# fpga-bank7.net
KiCad netlist of a schematic drawn in Altium Designer
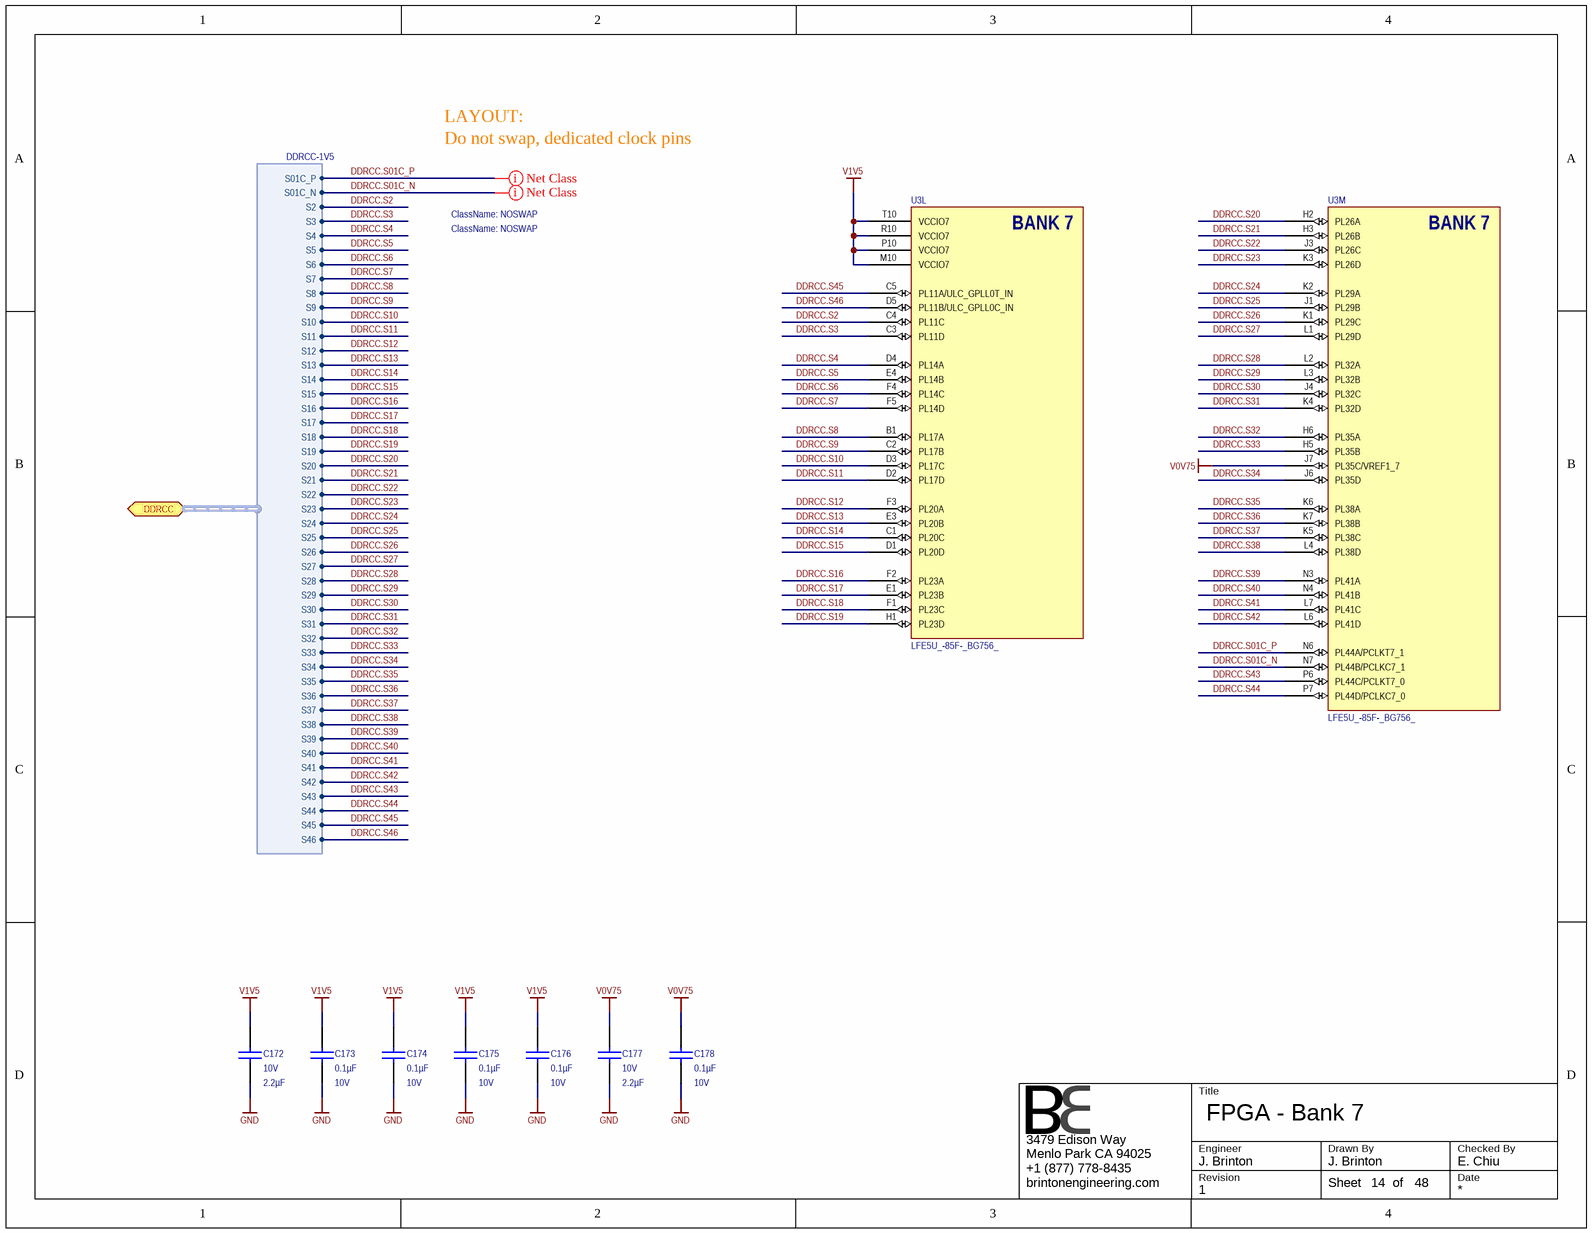
[diagram p0: fpga-bank7.SchDoc]

(export (version "E")
  (design (tool "Eeschema 10.0.6"))
  (components
    (comp (ref "C172")
      (value "GRM188R71A225KE15D")
      (footprint "CAPC1608X90N")
      (description "CAP CER 2.2UF 10V 10% X7R 0603")
      (fields
        (field (name "MANUFACTURER") "Murata Electronics North America")
        (field (name "TOLERANCE") "±10%")
        (field (name "VOLTAGE - RATED") "10V")
        (field (name "CAPACITANCE") "2.2µF")
      )
      (libsource (lib "murata") (part "GRM188R71A225KE15D"))
    )
    (comp (ref "C173")
      (value "GRM155R71A104KA01J")
      (footprint "CAPC1005X56N")
      (description "CAP CER 0.1UF 10V 10% X7R 0402")
      (fields
        (field (name "MANUFACTURER") "Murata Electronics North America")
        (field (name "TOLERANCE") "±10%")
        (field (name "CAPACITANCE") "0.1µF")
        (field (name "VOLTAGE - RATED") "10V")
      )
      (libsource (lib "murata") (part "GRM155R71A104KA01J"))
    )
    (comp (ref "C174")
      (value "GRM155R71A104KA01J")
      (footprint "CAPC1005X56N")
      (description "CAP CER 0.1UF 10V 10% X7R 0402")
      (fields
        (field (name "MANUFACTURER") "Murata Electronics North America")
        (field (name "TOLERANCE") "±10%")
        (field (name "CAPACITANCE") "0.1µF")
        (field (name "VOLTAGE - RATED") "10V")
      )
      (libsource (lib "murata") (part "GRM155R71A104KA01J"))
    )
    (comp (ref "C175")
      (value "GRM155R71A104KA01J")
      (footprint "CAPC1005X56N")
      (description "CAP CER 0.1UF 10V 10% X7R 0402")
      (fields
        (field (name "MANUFACTURER") "Murata Electronics North America")
        (field (name "TOLERANCE") "±10%")
        (field (name "CAPACITANCE") "0.1µF")
        (field (name "VOLTAGE - RATED") "10V")
      )
      (libsource (lib "murata") (part "GRM155R71A104KA01J"))
    )
    (comp (ref "C176")
      (value "GRM155R71A104KA01J")
      (footprint "CAPC1005X56N")
      (description "CAP CER 0.1UF 10V 10% X7R 0402")
      (fields
        (field (name "MANUFACTURER") "Murata Electronics North America")
        (field (name "TOLERANCE") "±10%")
        (field (name "CAPACITANCE") "0.1µF")
        (field (name "VOLTAGE - RATED") "10V")
      )
      (libsource (lib "murata") (part "GRM155R71A104KA01J"))
    )
    (comp (ref "C177")
      (value "GRM188R71A225KE15D")
      (footprint "CAPC1608X90N")
      (description "CAP CER 2.2UF 10V 10% X7R 0603")
      (fields
        (field (name "MANUFACTURER") "Murata Electronics North America")
        (field (name "TOLERANCE") "±10%")
        (field (name "VOLTAGE - RATED") "10V")
        (field (name "CAPACITANCE") "2.2µF")
      )
      (libsource (lib "murata") (part "GRM188R71A225KE15D"))
    )
    (comp (ref "C178")
      (value "GRM155R71A104KA01J")
      (footprint "CAPC1005X56N")
      (description "CAP CER 0.1UF 10V 10% X7R 0402")
      (fields
        (field (name "MANUFACTURER") "Murata Electronics North America")
        (field (name "TOLERANCE") "±10%")
        (field (name "CAPACITANCE") "0.1µF")
        (field (name "VOLTAGE - RATED") "10V")
      )
      (libsource (lib "murata") (part "GRM155R71A104KA01J"))
    )
    (comp (ref "U3")
      (value "LFE5U_-85F-_BG756_")
      (footprint "lattice:caBGA756")
      (description "ECP5 FPGA, 85k LUT, 756-caBGA")
      (fields (field (name "MANUFACTURER") "Lattice Semiconductor"))
      (libsource (lib "lattice") (part "LFE5U_-85F-_BG756_"))
    )
  )
  (nets
    (net (code "2") (name "/DDRCC.S01C_N") (class "Default")
      (node (ref "U3") (pin "N7") (pinfunction "PL44B/PCLKC7_1_N7") (pintype "bidirectional"))
    )
    (net (code "3") (name "/DDRCC.S01C_P") (class "Default")
      (node (ref "U3") (pin "N6") (pinfunction "PL44A/PCLKT7_1_N6") (pintype "bidirectional"))
    )
    (net (code "4") (name "/DDRCC.S2") (class "Default")
      (node (ref "U3") (pin "C4") (pinfunction "PL11C_C4") (pintype "bidirectional"))
    )
    (net (code "5") (name "/DDRCC.S3") (class "Default")
      (node (ref "U3") (pin "C3") (pinfunction "PL11D_C3") (pintype "bidirectional"))
    )
    (net (code "6") (name "/DDRCC.S4") (class "Default")
      (node (ref "U3") (pin "D4") (pinfunction "PL14A_D4") (pintype "bidirectional"))
    )
    (net (code "7") (name "/DDRCC.S5") (class "Default")
      (node (ref "U3") (pin "E4") (pinfunction "PL14B_E4") (pintype "bidirectional"))
    )
    (net (code "8") (name "/DDRCC.S6") (class "Default")
      (node (ref "U3") (pin "F4") (pinfunction "PL14C_F4") (pintype "bidirectional"))
    )
    (net (code "9") (name "/DDRCC.S7") (class "Default")
      (node (ref "U3") (pin "F5") (pinfunction "PL14D_F5") (pintype "bidirectional"))
    )
    (net (code "10") (name "/DDRCC.S8") (class "Default")
      (node (ref "U3") (pin "B1") (pinfunction "PL17A_B1") (pintype "bidirectional"))
    )
    (net (code "11") (name "/DDRCC.S9") (class "Default")
      (node (ref "U3") (pin "C2") (pinfunction "PL17B_C2") (pintype "bidirectional"))
    )
    (net (code "12") (name "/DDRCC.S10") (class "Default")
      (node (ref "U3") (pin "D3") (pinfunction "PL17C_D3") (pintype "bidirectional"))
    )
    (net (code "13") (name "/DDRCC.S11") (class "Default")
      (node (ref "U3") (pin "D2") (pinfunction "PL17D_D2") (pintype "bidirectional"))
    )
    (net (code "14") (name "/DDRCC.S12") (class "Default")
      (node (ref "U3") (pin "F3") (pinfunction "PL20A_F3") (pintype "bidirectional"))
    )
    (net (code "15") (name "/DDRCC.S13") (class "Default")
      (node (ref "U3") (pin "E3") (pinfunction "PL20B_E3") (pintype "bidirectional"))
    )
    (net (code "16") (name "/DDRCC.S14") (class "Default")
      (node (ref "U3") (pin "C1") (pinfunction "PL20C_C1") (pintype "bidirectional"))
    )
    (net (code "17") (name "/DDRCC.S15") (class "Default")
      (node (ref "U3") (pin "D1") (pinfunction "PL20D_D1") (pintype "bidirectional"))
    )
    (net (code "18") (name "/DDRCC.S16") (class "Default")
      (node (ref "U3") (pin "F2") (pinfunction "PL23A_F2") (pintype "bidirectional"))
    )
    (net (code "19") (name "/DDRCC.S17") (class "Default")
      (node (ref "U3") (pin "E1") (pinfunction "PL23B_E1") (pintype "bidirectional"))
    )
    (net (code "20") (name "/DDRCC.S18") (class "Default")
      (node (ref "U3") (pin "F1") (pinfunction "PL23C_F1") (pintype "bidirectional"))
    )
    (net (code "21") (name "/DDRCC.S19") (class "Default")
      (node (ref "U3") (pin "H1") (pinfunction "PL23D_H1") (pintype "bidirectional"))
    )
    (net (code "22") (name "/DDRCC.S20") (class "Default")
      (node (ref "U3") (pin "H2") (pinfunction "PL26A_H2") (pintype "bidirectional"))
    )
    (net (code "23") (name "/DDRCC.S21") (class "Default")
      (node (ref "U3") (pin "H3") (pinfunction "PL26B_H3") (pintype "bidirectional"))
    )
    (net (code "24") (name "/DDRCC.S22") (class "Default")
      (node (ref "U3") (pin "J3") (pinfunction "PL26C_J3") (pintype "bidirectional"))
    )
    (net (code "25") (name "/DDRCC.S23") (class "Default")
      (node (ref "U3") (pin "K3") (pinfunction "PL26D_K3") (pintype "bidirectional"))
    )
    (net (code "26") (name "/DDRCC.S24") (class "Default")
      (node (ref "U3") (pin "K2") (pinfunction "PL29A_K2") (pintype "bidirectional"))
    )
    (net (code "27") (name "/DDRCC.S25") (class "Default")
      (node (ref "U3") (pin "J1") (pinfunction "PL29B_J1") (pintype "bidirectional"))
    )
    (net (code "28") (name "/DDRCC.S26") (class "Default")
      (node (ref "U3") (pin "K1") (pinfunction "PL29C_K1") (pintype "bidirectional"))
    )
    (net (code "29") (name "/DDRCC.S27") (class "Default")
      (node (ref "U3") (pin "L1") (pinfunction "PL29D_L1") (pintype "bidirectional"))
    )
    (net (code "30") (name "/DDRCC.S28") (class "Default")
      (node (ref "U3") (pin "L2") (pinfunction "PL32A_L2") (pintype "bidirectional"))
    )
    (net (code "31") (name "/DDRCC.S29") (class "Default")
      (node (ref "U3") (pin "L3") (pinfunction "PL32B_L3") (pintype "bidirectional"))
    )
    (net (code "32") (name "/DDRCC.S30") (class "Default")
      (node (ref "U3") (pin "J4") (pinfunction "PL32C_J4") (pintype "bidirectional"))
    )
    (net (code "33") (name "/DDRCC.S31") (class "Default")
      (node (ref "U3") (pin "K4") (pinfunction "PL32D_K4") (pintype "bidirectional"))
    )
    (net (code "34") (name "/DDRCC.S32") (class "Default")
      (node (ref "U3") (pin "H6") (pinfunction "PL35A_H6") (pintype "bidirectional"))
    )
    (net (code "35") (name "/DDRCC.S33") (class "Default")
      (node (ref "U3") (pin "H5") (pinfunction "PL35B_H5") (pintype "bidirectional"))
    )
    (net (code "36") (name "/DDRCC.S34") (class "Default")
      (node (ref "U3") (pin "J6") (pinfunction "PL35D_J6") (pintype "bidirectional"))
    )
    (net (code "37") (name "/DDRCC.S35") (class "Default")
      (node (ref "U3") (pin "K6") (pinfunction "PL38A_K6") (pintype "bidirectional"))
    )
    (net (code "38") (name "/DDRCC.S36") (class "Default")
      (node (ref "U3") (pin "K7") (pinfunction "PL38B_K7") (pintype "bidirectional"))
    )
    (net (code "39") (name "/DDRCC.S37") (class "Default")
      (node (ref "U3") (pin "K5") (pinfunction "PL38C_K5") (pintype "bidirectional"))
    )
    (net (code "40") (name "/DDRCC.S38") (class "Default")
      (node (ref "U3") (pin "L4") (pinfunction "PL38D_L4") (pintype "bidirectional"))
    )
    (net (code "41") (name "/DDRCC.S39") (class "Default")
      (node (ref "U3") (pin "N3") (pinfunction "PL41A_N3") (pintype "bidirectional"))
    )
    (net (code "42") (name "/DDRCC.S40") (class "Default")
      (node (ref "U3") (pin "N4") (pinfunction "PL41B_N4") (pintype "bidirectional"))
    )
    (net (code "43") (name "/DDRCC.S41") (class "Default")
      (node (ref "U3") (pin "L7") (pinfunction "PL41C_L7") (pintype "bidirectional"))
    )
    (net (code "44") (name "/DDRCC.S42") (class "Default")
      (node (ref "U3") (pin "L6") (pinfunction "PL41D_L6") (pintype "bidirectional"))
    )
    (net (code "45") (name "/DDRCC.S43") (class "Default")
      (node (ref "U3") (pin "P6") (pinfunction "PL44C/PCLKT7_0_P6") (pintype "bidirectional"))
    )
    (net (code "46") (name "/DDRCC.S44") (class "Default")
      (node (ref "U3") (pin "P7") (pinfunction "PL44D/PCLKC7_0_P7") (pintype "bidirectional"))
    )
    (net (code "47") (name "/DDRCC.S45") (class "Default")
      (node (ref "U3") (pin "C5") (pinfunction "PL11A/ULC_GPLL0T_IN_C5") (pintype "bidirectional"))
    )
    (net (code "48") (name "/DDRCC.S46") (class "Default")
      (node (ref "U3") (pin "D5") (pinfunction "PL11B/ULC_GPLL0C_IN_D5") (pintype "bidirectional"))
    )
    (net (code "50") (name "GND") (class "Default")
      (node (ref "C172") (pin "1") (pinfunction "1_1") (pintype "passive"))
      (node (ref "C173") (pin "1") (pinfunction "1_1") (pintype "passive"))
      (node (ref "C174") (pin "1") (pinfunction "1_1") (pintype "passive"))
      (node (ref "C175") (pin "1") (pinfunction "1_1") (pintype "passive"))
      (node (ref "C176") (pin "1") (pinfunction "1_1") (pintype "passive"))
      (node (ref "C177") (pin "1") (pinfunction "1_1") (pintype "passive"))
      (node (ref "C178") (pin "1") (pinfunction "1_1") (pintype "passive"))
    )
    (net (code "51") (name "V0V75") (class "Default")
      (node (ref "C177") (pin "2") (pinfunction "2_2") (pintype "passive"))
      (node (ref "C178") (pin "2") (pinfunction "2_2") (pintype "passive"))
      (node (ref "U3") (pin "J7") (pinfunction "PL35C/VREF1_7_J7") (pintype "bidirectional"))
    )
    (net (code "52") (name "V1V5") (class "Default")
      (node (ref "C172") (pin "2") (pinfunction "2_2") (pintype "passive"))
      (node (ref "C173") (pin "2") (pinfunction "2_2") (pintype "passive"))
      (node (ref "C174") (pin "2") (pinfunction "2_2") (pintype "passive"))
      (node (ref "C175") (pin "2") (pinfunction "2_2") (pintype "passive"))
      (node (ref "C176") (pin "2") (pinfunction "2_2") (pintype "passive"))
      (node (ref "U3") (pin "M10") (pinfunction "VCCIO7_M10") (pintype "power_in"))
      (node (ref "U3") (pin "P10") (pinfunction "VCCIO7_P10") (pintype "power_in"))
      (node (ref "U3") (pin "R10") (pinfunction "VCCIO7_R10") (pintype "power_in"))
      (node (ref "U3") (pin "T10") (pinfunction "VCCIO7_T10") (pintype "power_in"))
    )
  )
)
